# 2_ADST32-MCU.net
KiCad netlist of a schematic drawn in Altium Designer
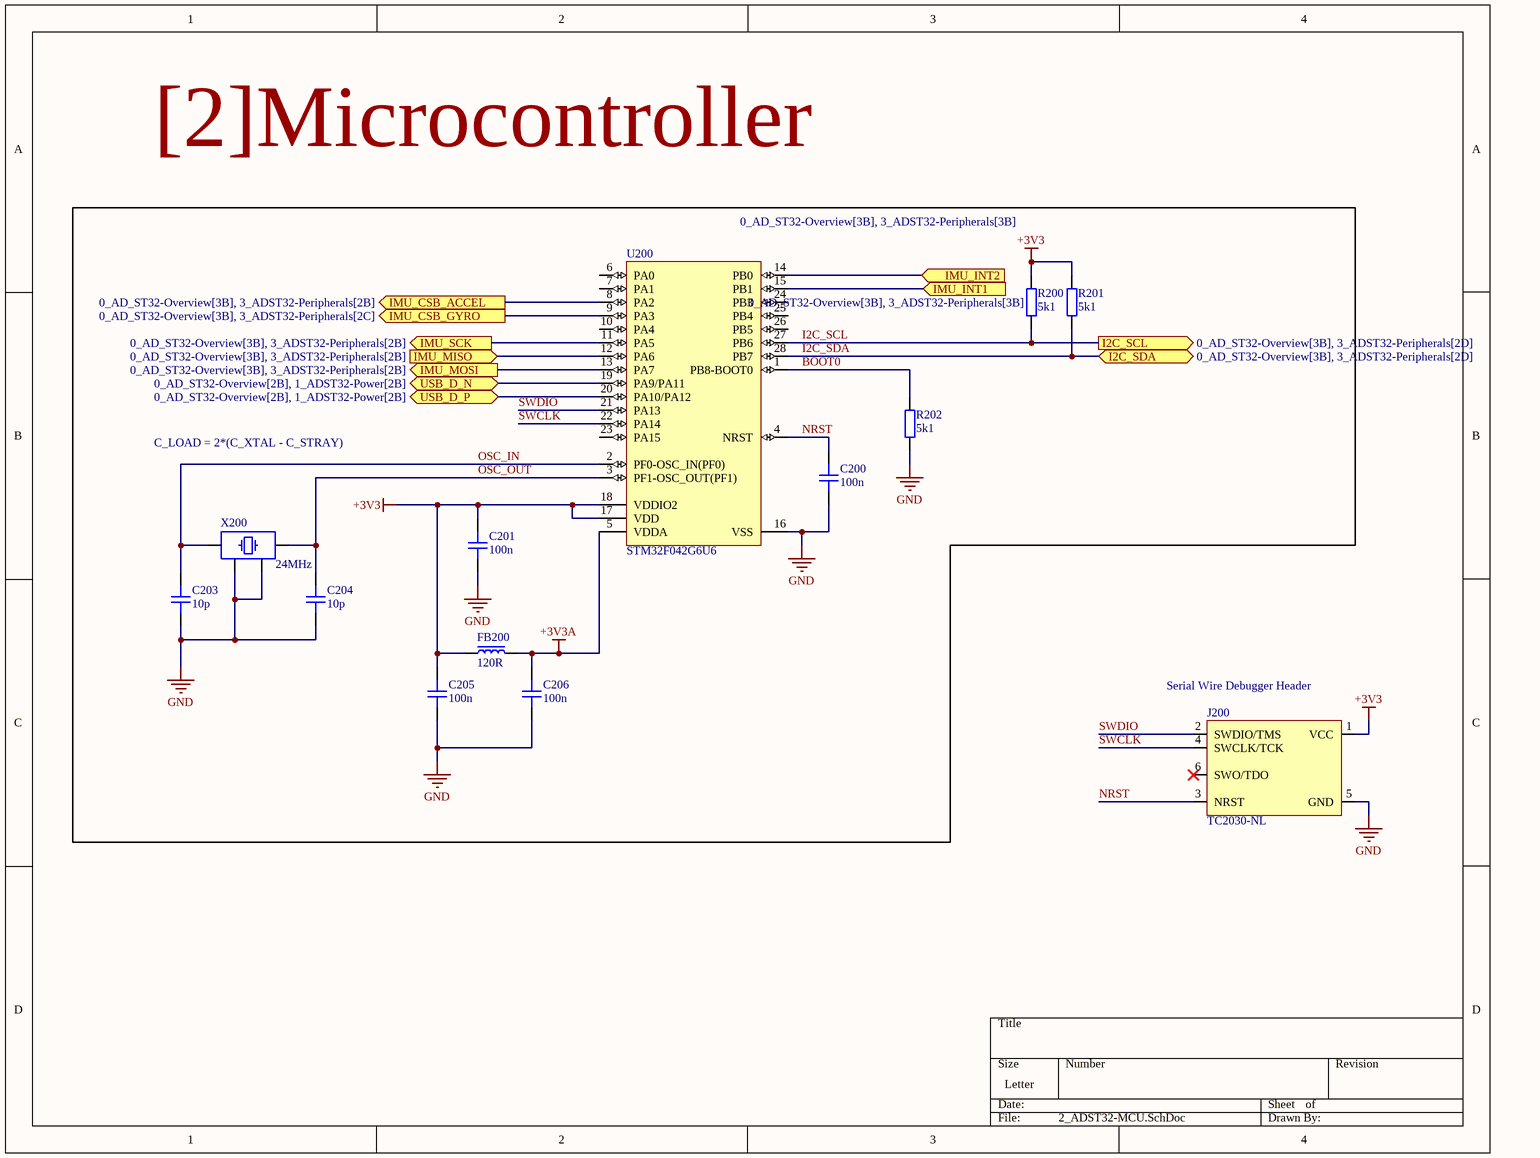
[diagram p0: 2_ADST32-MCU.SchDoc]

(export (version "E")
  (design (tool "Eeschema 10.0.6"))
  (components
    (comp (ref "C200")
      (value "100n")
      (footprint "CAP_0603")
      (description "Capacitor SMD 0603")
      (libsource (lib "Schematic-Lib-PhilsLab") (part "CAP_0603"))
    )
    (comp (ref "C201")
      (value "100n")
      (footprint "CAP_0603")
      (description "Capacitor SMD 0603")
      (libsource (lib "Schematic-Lib-PhilsLab") (part "CAP_0603"))
    )
    (comp (ref "C203")
      (value "10p")
      (footprint "CAP_0603")
      (description "Capacitor SMD 0603")
      (libsource (lib "Schematic-Lib-PhilsLab") (part "CAP_0603"))
    )
    (comp (ref "C204")
      (value "10p")
      (footprint "CAP_0603")
      (description "Capacitor SMD 0603")
      (libsource (lib "Schematic-Lib-PhilsLab") (part "CAP_0603"))
    )
    (comp (ref "C205")
      (value "100n")
      (footprint "CAP_0603")
      (description "Capacitor SMD 0603")
      (libsource (lib "Schematic-Lib-PhilsLab") (part "CAP_0603"))
    )
    (comp (ref "C206")
      (value "100n")
      (footprint "CAP_0603")
      (description "Capacitor SMD 0603")
      (libsource (lib "Schematic-Lib-PhilsLab") (part "CAP_0603"))
    )
    (comp (ref "FB200")
      (value "120R")
      (footprint "FB_0603")
      (description "Ferrite Bead SMD 0603")
      (libsource (lib "Schematic-Lib-PhilsLab") (part "FB_0603"))
    )
    (comp (ref "J200")
      (value "TC2030-NL")
      (footprint "TC2030-NL-FP")
      (description "Tag-Connect No-Solder SWD Debug Connector (No Legs) DO NOT PLACE")
      (fields
        (field (name "MANUFACTURER") "Tag-Connect")
        (field (name "MANUFACTURER PART NUMBER") "TC2030-NL-FP")
      )
      (libsource (lib "Schematic-Lib-PhilsLab") (part "TC2030-NL"))
    )
    (comp (ref "R200")
      (value "5k1")
      (footprint "RES_0603")
      (description "Resistor SMD 0603")
      (libsource (lib "Schematic-Lib-PhilsLab") (part "RES_0603"))
    )
    (comp (ref "R201")
      (value "5k1")
      (footprint "RES_0603")
      (description "Resistor SMD 0603")
      (libsource (lib "Schematic-Lib-PhilsLab") (part "RES_0603"))
    )
    (comp (ref "R202")
      (value "5k1")
      (footprint "RES_0603")
      (description "Resistor SMD 0603")
      (libsource (lib "Schematic-Lib-PhilsLab") (part "RES_0603"))
    )
    (comp (ref "U200")
      (value "STM32F042G6U6")
      (footprint "STM-UFQFPN28_V")
      (fields (field (name "MANUFACTURER") "STMicroelectronics"))
      (libsource (lib "Altium Content Vault") (part "MC-ARM-STM32F042-UFQFPN28"))
    )
    (comp (ref "X200")
      (value "24MHz")
      (footprint "XTAL_3225")
      (description "Crystal SMD 24MHz 10PPM 7pF 3225")
      (fields
        (field (name "MANUFACTURER") "Epson")
        (field (name "MANUFACTURER PART NUMBER") "TSX-3225 24.0000MF15X-AC")
      )
      (libsource (lib "Schematic-Lib-PhilsLab") (part "TSX-3225_24.0000MF15X-AC"))
    )
  )
  (nets
    (net (code "1") (name "+3V3") (class "Default")
      (node (ref "C201") (pin "2") (pinfunction "2_2") (pintype "passive"))
      (node (ref "C205") (pin "2") (pinfunction "2_2") (pintype "passive"))
      (node (ref "FB200") (pin "1") (pinfunction "1_1") (pintype "passive"))
      (node (ref "J200") (pin "1") (pinfunction "VCC_1") (pintype "passive"))
      (node (ref "R200") (pin "2") (pinfunction "2_2") (pintype "passive"))
      (node (ref "R201") (pin "2") (pinfunction "2_2") (pintype "passive"))
      (node (ref "U200") (pin "17") (pinfunction "VDD_17") (pintype "power_in"))
      (node (ref "U200") (pin "18") (pinfunction "VDDIO2_18") (pintype "power_in"))
    )
    (net (code "2") (name "+3V3A") (class "Default")
      (node (ref "C206") (pin "2") (pinfunction "2_2") (pintype "passive"))
      (node (ref "FB200") (pin "2") (pinfunction "2_2") (pintype "passive"))
      (node (ref "U200") (pin "5") (pinfunction "VDDA_5") (pintype "power_in"))
    )
    (net (code "3") (name "/BOOT0") (class "Default")
      (node (ref "R202") (pin "2") (pinfunction "2_2") (pintype "passive"))
      (node (ref "U200") (pin "1") (pinfunction "PB8-BOOT0_1") (pintype "bidirectional"))
    )
    (net (code "4") (name "/I2C_SCL") (class "Default")
      (node (ref "R200") (pin "1") (pinfunction "1_1") (pintype "passive"))
      (node (ref "U200") (pin "27") (pinfunction "PB6_27") (pintype "bidirectional"))
    )
    (net (code "5") (name "/I2C_SDA") (class "Default")
      (node (ref "R201") (pin "1") (pinfunction "1_1") (pintype "passive"))
      (node (ref "U200") (pin "28") (pinfunction "PB7_28") (pintype "bidirectional"))
    )
    (net (code "6") (name "/IMU_CSB_ACCEL") (class "Default")
      (node (ref "U200") (pin "8") (pinfunction "PA2_8") (pintype "bidirectional"))
    )
    (net (code "7") (name "/IMU_CSB_GYRO") (class "Default")
      (node (ref "U200") (pin "9") (pinfunction "PA3_9") (pintype "bidirectional"))
    )
    (net (code "8") (name "/IMU_INT1") (class "Default")
      (node (ref "U200") (pin "15") (pinfunction "PB1_15") (pintype "bidirectional"))
    )
    (net (code "9") (name "/IMU_INT2") (class "Default")
      (node (ref "U200") (pin "14") (pinfunction "PB0_14") (pintype "bidirectional"))
    )
    (net (code "10") (name "/IMU_MISO") (class "Default")
      (node (ref "U200") (pin "12") (pinfunction "PA6_12") (pintype "bidirectional"))
    )
    (net (code "11") (name "/IMU_MOSI") (class "Default")
      (node (ref "U200") (pin "13") (pinfunction "PA7_13") (pintype "bidirectional"))
    )
    (net (code "12") (name "/IMU_SCK") (class "Default")
      (node (ref "U200") (pin "11") (pinfunction "PA5_11") (pintype "bidirectional"))
    )
    (net (code "13") (name "/NRST") (class "Default")
      (node (ref "C200") (pin "2") (pinfunction "2_2") (pintype "passive"))
      (node (ref "J200") (pin "3") (pinfunction "NRST_3") (pintype "passive"))
      (node (ref "U200") (pin "4") (pinfunction "NRST_4") (pintype "bidirectional"))
    )
    (net (code "14") (name "/OSC_IN") (class "Default")
      (node (ref "C203") (pin "2") (pinfunction "2_2") (pintype "passive"))
      (node (ref "U200") (pin "2") (pinfunction "PF0-OSC_IN(PF0)_2") (pintype "bidirectional"))
      (node (ref "X200") (pin "1") (pinfunction "1_1") (pintype "passive"))
    )
    (net (code "15") (name "/OSC_OUT") (class "Default")
      (node (ref "C204") (pin "2") (pinfunction "2_2") (pintype "passive"))
      (node (ref "U200") (pin "3") (pinfunction "PF1-OSC_OUT(PF1)_3") (pintype "bidirectional"))
      (node (ref "X200") (pin "3") (pinfunction "3_3") (pintype "passive"))
    )
    (net (code "16") (name "/SWCLK") (class "Default")
      (node (ref "J200") (pin "4") (pinfunction "SWCLK/TCK_4") (pintype "passive"))
      (node (ref "U200") (pin "22") (pinfunction "PA14_22") (pintype "bidirectional"))
    )
    (net (code "17") (name "/SWDIO") (class "Default")
      (node (ref "J200") (pin "2") (pinfunction "SWDIO/TMS_2") (pintype "passive"))
      (node (ref "U200") (pin "21") (pinfunction "PA13_21") (pintype "bidirectional"))
    )
    (net (code "18") (name "/USB_D_N") (class "Default")
      (node (ref "U200") (pin "19") (pinfunction "PA9/PA11_19") (pintype "bidirectional"))
    )
    (net (code "19") (name "/USB_D_P") (class "Default")
      (node (ref "U200") (pin "20") (pinfunction "PA10/PA12_20") (pintype "bidirectional"))
    )
    (net (code "20") (name "GND") (class "Default")
      (node (ref "C200") (pin "1") (pinfunction "1_1") (pintype "passive"))
      (node (ref "C201") (pin "1") (pinfunction "1_1") (pintype "passive"))
      (node (ref "C203") (pin "1") (pinfunction "1_1") (pintype "passive"))
      (node (ref "C204") (pin "1") (pinfunction "1_1") (pintype "passive"))
      (node (ref "C205") (pin "1") (pinfunction "1_1") (pintype "passive"))
      (node (ref "C206") (pin "1") (pinfunction "1_1") (pintype "passive"))
      (node (ref "J200") (pin "5") (pinfunction "GND_5") (pintype "passive"))
      (node (ref "R202") (pin "1") (pinfunction "1_1") (pintype "passive"))
      (node (ref "U200") (pin "16") (pinfunction "VSS_16") (pintype "power_in"))
      (node (ref "X200") (pin "2") (pinfunction "2_2") (pintype "passive"))
      (node (ref "X200") (pin "4") (pinfunction "4_4") (pintype "passive"))
    )
    (net (code "21") (name "unconnected-(J200-SWO{slash}TDO-Pad6)") (class "Default")
      (node (ref "J200") (pin "6") (pinfunction "SWO/TDO_6") (pintype "passive+no_connect"))
    )
    (net (code "22") (name "unconnected-(U200-PA0-Pad6)") (class "Default")
      (node (ref "U200") (pin "6") (pinfunction "PA0_6") (pintype "bidirectional"))
    )
    (net (code "23") (name "unconnected-(U200-PA1-Pad7)") (class "Default")
      (node (ref "U200") (pin "7") (pinfunction "PA1_7") (pintype "bidirectional"))
    )
    (net (code "24") (name "unconnected-(U200-PA4-Pad10)") (class "Default")
      (node (ref "U200") (pin "10") (pinfunction "PA4_10") (pintype "bidirectional"))
    )
    (net (code "25") (name "unconnected-(U200-PA15-Pad23)") (class "Default")
      (node (ref "U200") (pin "23") (pinfunction "PA15_23") (pintype "bidirectional"))
    )
    (net (code "26") (name "unconnected-(U200-PB3-Pad24)") (class "Default")
      (node (ref "U200") (pin "24") (pinfunction "PB3_24") (pintype "bidirectional"))
    )
    (net (code "27") (name "unconnected-(U200-PB4-Pad25)") (class "Default")
      (node (ref "U200") (pin "25") (pinfunction "PB4_25") (pintype "bidirectional"))
    )
    (net (code "28") (name "unconnected-(U200-PB5-Pad26)") (class "Default")
      (node (ref "U200") (pin "26") (pinfunction "PB5_26") (pintype "bidirectional"))
    )
  )
)
